# Design.net
KiCad netlist of a schematic drawn in EAGLE
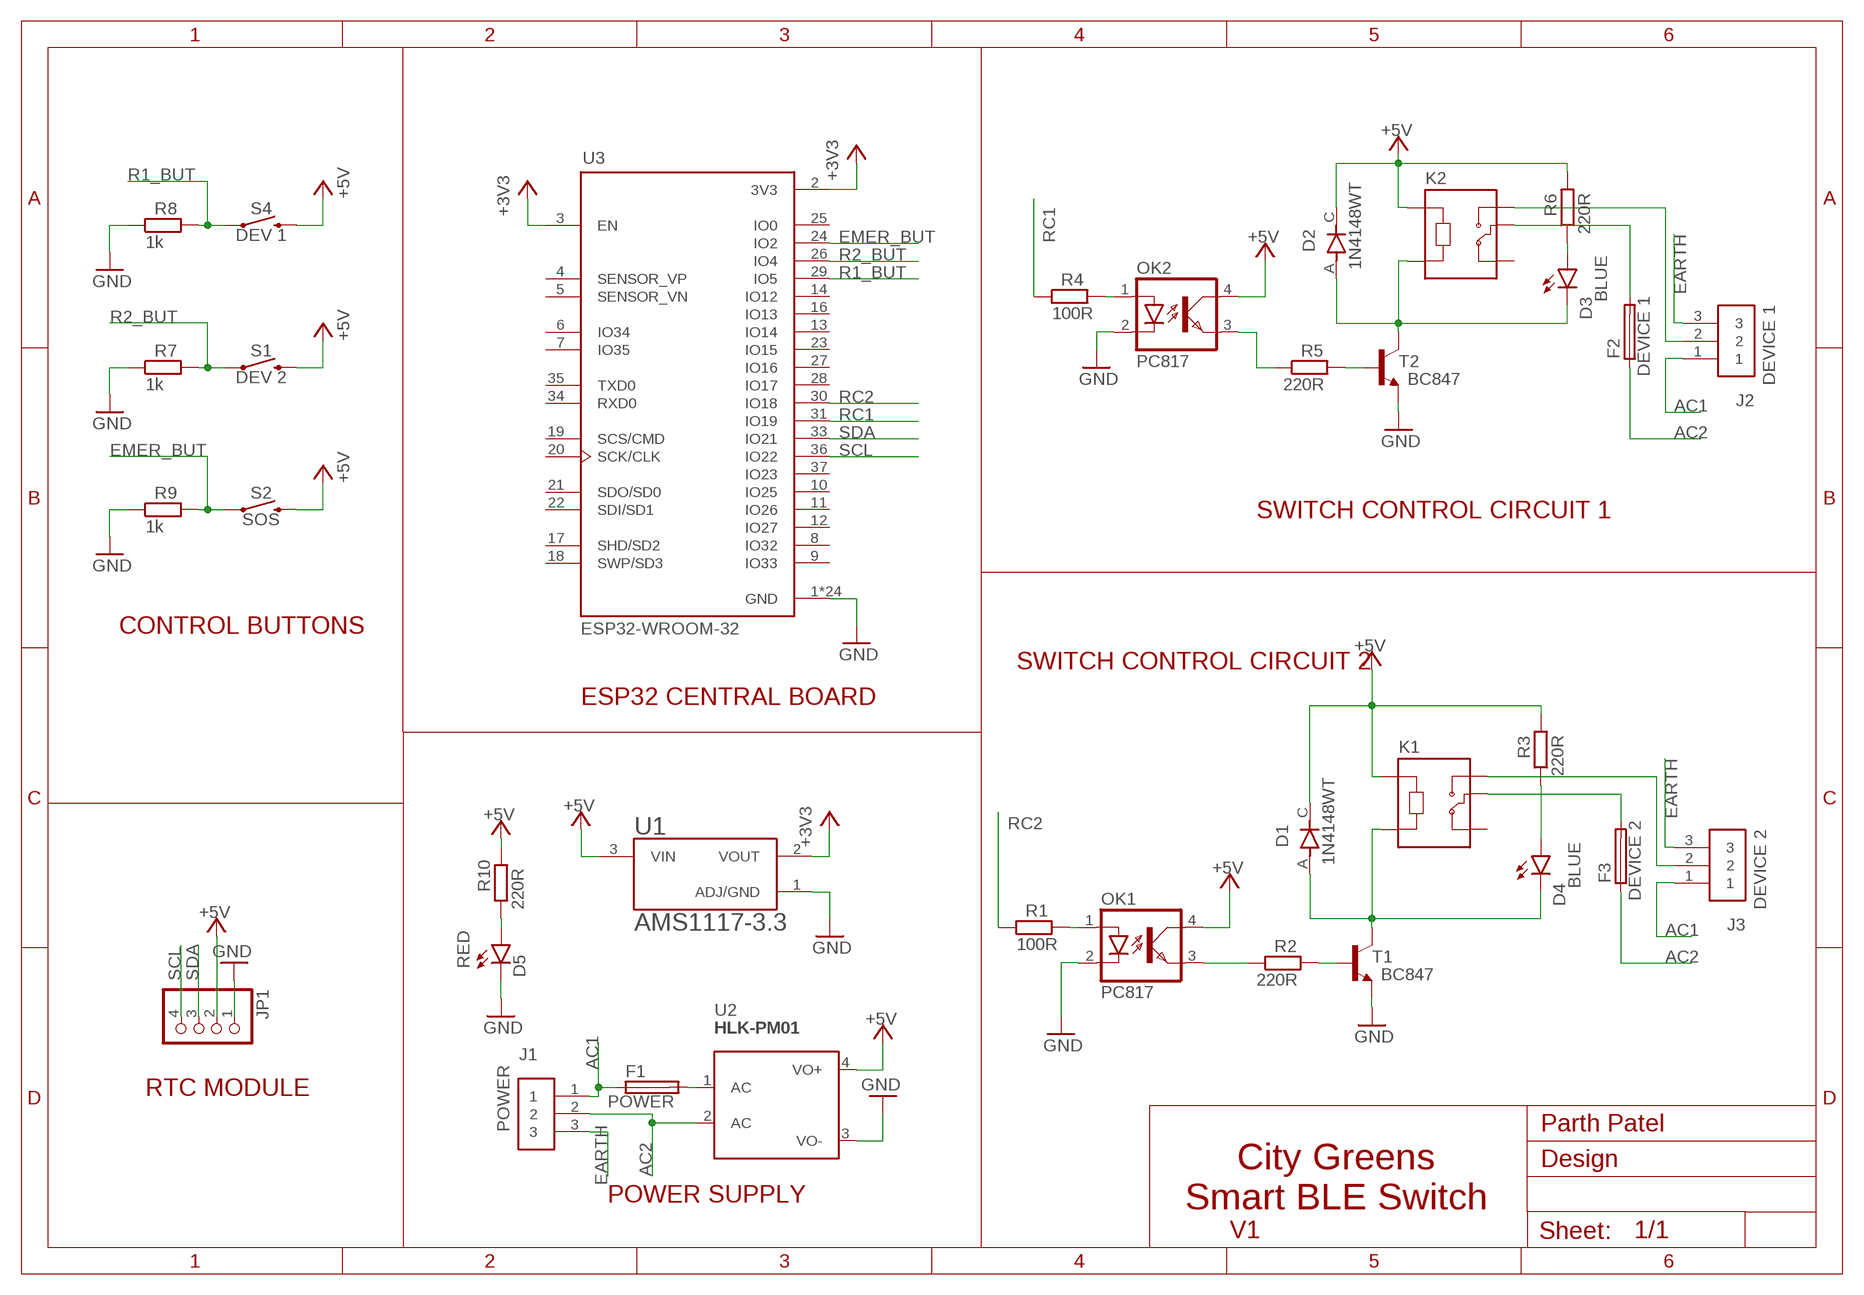
[diagram p0: schematic, sheet 1]

(export (version "E")
  (design (tool "Eeschema 10.0.6"))
  (components
    (comp (ref "D1")
      (value "1N4148WT")
      (footprint "eagle-import:SODFL1608X70N")
      (fields (field (name "MF") "ON Semiconductor"))
      (libsource (lib "eagle-import") (part "1N4148WT"))
    )
    (comp (ref "D2")
      (value "1N4148WT")
      (footprint "eagle-import:SODFL1608X70N")
      (fields (field (name "MF") "ON Semiconductor") (field (name "SPICEPREFIX") "D"))
      (libsource (lib "eagle-import") (part "1N4148WT"))
    )
    (comp (ref "D3")
      (value "BLUE")
      (footprint "eagle-import:CHIP-LED0603")
      (libsource (lib "eagle-import") (part "LEDCHIP-LED0603"))
    )
    (comp (ref "D4")
      (value "BLUE")
      (footprint "eagle-import:CHIP-LED0603")
      (libsource (lib "eagle-import") (part "LEDCHIP-LED0603"))
    )
    (comp (ref "D5")
      (value "RED")
      (footprint "eagle-import:CHIP-LED0603")
      (libsource (lib "eagle-import") (part "LEDCHIP-LED0603"))
    )
    (comp (ref "F1")
      (value "POWER")
      (footprint "eagle-import:TE5")
      (libsource (lib "eagle-import") (part "TE5"))
    )
    (comp (ref "F2")
      (value "DEVICE 1")
      (footprint "eagle-import:TE5")
      (libsource (lib "eagle-import") (part "TE5"))
    )
    (comp (ref "F3")
      (value "DEVICE 2")
      (footprint "eagle-import:TE5")
      (libsource (lib "eagle-import") (part "TE5"))
    )
    (comp (ref "J1")
      (value "POWER")
      (footprint "eagle-import:TERMINALBLOCK_PLUGGABLE-3-7.62MM")
      (fields
        (field (name "DIGIKEY_PART_NO") "732-2824-ND")
        (field (name "MANUFACTURER") "WURTH ELEKTRONIK")
        (field (name "MPN") "691311400103")
        (field (name "CREATED_BY") "PCBLayout.com")
      )
      (libsource (lib "eagle-import") (part "691311400103"))
    )
    (comp (ref "J2")
      (value "DEVICE 1")
      (footprint "eagle-import:TERMINALBLOCK_PLUGGABLE-3-7.62MM")
      (fields
        (field (name "DIGIKEY_PART_NO") "732-2824-ND")
        (field (name "MANUFACTURER") "WURTH ELEKTRONIK")
        (field (name "MPN") "691311400103")
        (field (name "CREATED_BY") "PCBLayout.com")
      )
      (libsource (lib "eagle-import") (part "691311400103"))
    )
    (comp (ref "J3")
      (value "DEVICE 2")
      (footprint "eagle-import:TERMINALBLOCK_PLUGGABLE-3-7.62MM")
      (fields
        (field (name "DIGIKEY_PART_NO") "732-2824-ND")
        (field (name "MANUFACTURER") "WURTH ELEKTRONIK")
        (field (name "MPN") "691311400103")
        (field (name "CREATED_BY") "PCBLayout.com")
      )
      (libsource (lib "eagle-import") (part "691311400103"))
    )
    (comp (ref "JP1")
      (value "PINHD-1X4")
      (footprint "eagle-import:1X04")
      (libsource (lib "eagle-import") (part "PINHD-1X4"))
    )
    (comp (ref "K1")
      (value "SRD-05VDC-SL-C")
      (footprint "eagle-import:RELAY_SRD-05VDC-SL-C")
      (fields (field (name "MF") "Songle Relay"))
      (libsource (lib "eagle-import") (part "SRD-05VDC-SL-C"))
    )
    (comp (ref "K2")
      (value "SRD-05VDC-SL-C")
      (footprint "eagle-import:RELAY_SRD-05VDC-SL-C")
      (fields (field (name "MF") "Songle Relay"))
      (libsource (lib "eagle-import") (part "SRD-05VDC-SL-C"))
    )
    (comp (ref "OK1")
      (value "PC817")
      (footprint "eagle-import:DIL04")
      (fields (field (name "MPN") "PC817X4J000F"))
      (libsource (lib "eagle-import") (part "PC817"))
    )
    (comp (ref "OK2")
      (value "PC817")
      (footprint "eagle-import:DIL04")
      (fields (field (name "MPN") "PC817X4J000F"))
      (libsource (lib "eagle-import") (part "PC817"))
    )
    (comp (ref "R1")
      (value "100R")
      (footprint "eagle-import:R0805")
      (libsource (lib "eagle-import") (part "R-EU_R0805"))
    )
    (comp (ref "R2")
      (value "220R")
      (footprint "eagle-import:R0805")
      (libsource (lib "eagle-import") (part "R-EU_R0805"))
    )
    (comp (ref "R3")
      (value "220R")
      (footprint "eagle-import:R0805")
      (libsource (lib "eagle-import") (part "R-EU_R0805"))
    )
    (comp (ref "R4")
      (value "100R")
      (footprint "eagle-import:R0805")
      (libsource (lib "eagle-import") (part "R-EU_R0805"))
    )
    (comp (ref "R5")
      (value "220R")
      (footprint "eagle-import:R0805")
      (libsource (lib "eagle-import") (part "R-EU_R0805"))
    )
    (comp (ref "R6")
      (value "220R")
      (footprint "eagle-import:R0805")
      (libsource (lib "eagle-import") (part "R-EU_R0805"))
    )
    (comp (ref "R7")
      (value "1k")
      (footprint "eagle-import:R0805")
      (libsource (lib "eagle-import") (part "R-EU_R0805"))
    )
    (comp (ref "R8")
      (value "1k")
      (footprint "eagle-import:R0805")
      (libsource (lib "eagle-import") (part "R-EU_R0805"))
    )
    (comp (ref "R9")
      (value "1k")
      (footprint "eagle-import:R0805")
      (libsource (lib "eagle-import") (part "R-EU_R0805"))
    )
    (comp (ref "R10")
      (value "220R")
      (footprint "eagle-import:R0805")
      (libsource (lib "eagle-import") (part "R-EU_R0805"))
    )
    (comp (ref "S1")
      (value "DEV 2")
      (footprint "eagle-import:TACTILE_SWITCH_SMD_4.5MM")
      (libsource (lib "eagle-import") (part "MOMENTARY-SWITCH-SPST-SMD-4.5MM"))
    )
    (comp (ref "S2")
      (value "SOS")
      (footprint "eagle-import:TACTILE_SWITCH_SMD_4.5MM")
      (libsource (lib "eagle-import") (part "MOMENTARY-SWITCH-SPST-SMD-4.5MM"))
    )
    (comp (ref "S4")
      (value "DEV 1")
      (footprint "eagle-import:TACTILE_SWITCH_SMD_4.5MM")
      (libsource (lib "eagle-import") (part "MOMENTARY-SWITCH-SPST-SMD-4.5MM"))
    )
    (comp (ref "T1")
      (value "BC847")
      (footprint "eagle-import:SOT23")
      (libsource (lib "eagle-import") (part "BC847"))
    )
    (comp (ref "T2")
      (value "BC847")
      (footprint "eagle-import:SOT23")
      (libsource (lib "eagle-import") (part "BC847"))
    )
    (comp (ref "U1")
      (value "AMS1117-3.3")
      (footprint "eagle-import:SOT229P700X180-4N")
      (fields (field (name "MF") "AMD"))
      (libsource (lib "eagle-import") (part "AMS1117-3.3"))
    )
    (comp (ref "U2")
      (value "HLK-PM01")
      (footprint "eagle-import:HLK-PM01")
      (fields (field (name "MF") "Hi-link") (field (name "MP") "hlk-pm01"))
      (libsource (lib "eagle-import") (part "HLK-PM01"))
    )
    (comp (ref "U3")
      (value "ESP32-WROOM-32")
      (footprint "eagle-import:MODULE_ESP32-WROOM-32")
      (fields (field (name "MF") "Espressif Systems"))
      (libsource (lib "eagle-import") (part "ESP32-WROOM-32"))
    )
  )
  (nets
    (net (code "1") (name "+3V3") (class "Default")
      (node (ref "U1") (pin "2") (pinfunction "VOUT_2") (pintype "output"))
      (node (ref "U3") (pin "2") (pinfunction "3V3_2") (pintype "power_in"))
      (node (ref "U3") (pin "3") (pinfunction "EN_3") (pintype "input"))
    )
    (net (code "2") (name "+5V") (class "Default")
      (node (ref "D1") (pin "C") (pinfunction "C_C") (pintype "passive"))
      (node (ref "D2") (pin "C") (pinfunction "C_C") (pintype "passive"))
      (node (ref "JP1") (pin "2") (pinfunction "2_2") (pintype "passive"))
      (node (ref "K1") (pin "A1") (pinfunction "A1_A1") (pintype "passive"))
      (node (ref "K2") (pin "A1") (pinfunction "A1_A1") (pintype "passive"))
      (node (ref "OK1") (pin "4") (pinfunction "COL_4") (pintype "passive"))
      (node (ref "OK2") (pin "4") (pinfunction "COL_4") (pintype "passive"))
      (node (ref "R10") (pin "2") (pinfunction "2_2") (pintype "passive"))
      (node (ref "R3") (pin "2") (pinfunction "2_2") (pintype "passive"))
      (node (ref "R6") (pin "2") (pinfunction "2_2") (pintype "passive"))
      (node (ref "S1") (pin "1") (pinfunction "2_1") (pintype "passive"))
      (node (ref "S1") (pin "4") (pinfunction "2_4") (pintype "passive"))
      (node (ref "S2") (pin "1") (pinfunction "2_1") (pintype "passive"))
      (node (ref "S2") (pin "4") (pinfunction "2_4") (pintype "passive"))
      (node (ref "S4") (pin "1") (pinfunction "2_1") (pintype "passive"))
      (node (ref "S4") (pin "4") (pinfunction "2_4") (pintype "passive"))
      (node (ref "U1") (pin "3") (pinfunction "VIN_3") (pintype "input"))
      (node (ref "U2") (pin "4") (pinfunction "VO+_4") (pintype "bidirectional"))
    )
    (net (code "3") (name "/AC1") (class "Default")
      (node (ref "F1") (pin "1") (pinfunction "1_1") (pintype "passive"))
      (node (ref "J1") (pin "1") (pinfunction "1_1") (pintype "passive"))
      (node (ref "J2") (pin "1") (pinfunction "1_1") (pintype "passive"))
      (node (ref "J3") (pin "1") (pinfunction "1_1") (pintype "passive"))
    )
    (net (code "4") (name "/AC2") (class "Default")
      (node (ref "F2") (pin "1") (pinfunction "1_1") (pintype "passive"))
      (node (ref "F3") (pin "1") (pinfunction "1_1") (pintype "passive"))
      (node (ref "J1") (pin "2") (pinfunction "2_2") (pintype "passive"))
      (node (ref "U2") (pin "2") (pinfunction "AC_2") (pintype "bidirectional"))
    )
    (net (code "5") (name "/EARTH") (class "Default")
      (node (ref "J1") (pin "3") (pinfunction "3_3") (pintype "passive"))
      (node (ref "J2") (pin "3") (pinfunction "3_3") (pintype "passive"))
      (node (ref "J3") (pin "3") (pinfunction "3_3") (pintype "passive"))
    )
    (net (code "6") (name "/EMER_BUT") (class "Default")
      (node (ref "R9") (pin "2") (pinfunction "2_2") (pintype "passive"))
      (node (ref "S2") (pin "2") (pinfunction "1_2") (pintype "passive"))
      (node (ref "S2") (pin "3") (pinfunction "1_3") (pintype "passive"))
      (node (ref "U3") (pin "24") (pinfunction "IO2_24") (pintype "bidirectional"))
    )
    (net (code "7") (name "/R1_BUT") (class "Default")
      (node (ref "R8") (pin "2") (pinfunction "2_2") (pintype "passive"))
      (node (ref "S4") (pin "2") (pinfunction "1_2") (pintype "passive"))
      (node (ref "S4") (pin "3") (pinfunction "1_3") (pintype "passive"))
      (node (ref "U3") (pin "29") (pinfunction "IO5_29") (pintype "bidirectional"))
    )
    (net (code "8") (name "/R2_BUT") (class "Default")
      (node (ref "R7") (pin "2") (pinfunction "2_2") (pintype "passive"))
      (node (ref "S1") (pin "2") (pinfunction "1_2") (pintype "passive"))
      (node (ref "S1") (pin "3") (pinfunction "1_3") (pintype "passive"))
      (node (ref "U3") (pin "26") (pinfunction "IO4_26") (pintype "bidirectional"))
    )
    (net (code "9") (name "/RC1") (class "Default")
      (node (ref "R4") (pin "1") (pinfunction "1_1") (pintype "passive"))
      (node (ref "U3") (pin "31") (pinfunction "IO19_31") (pintype "bidirectional"))
    )
    (net (code "10") (name "/RC2") (class "Default")
      (node (ref "R1") (pin "1") (pinfunction "1_1") (pintype "passive"))
      (node (ref "U3") (pin "30") (pinfunction "IO18_30") (pintype "bidirectional"))
    )
    (net (code "11") (name "/SCL") (class "Default")
      (node (ref "JP1") (pin "4") (pinfunction "4_4") (pintype "passive"))
      (node (ref "U3") (pin "36") (pinfunction "IO22_36") (pintype "bidirectional"))
    )
    (net (code "12") (name "/SDA") (class "Default")
      (node (ref "JP1") (pin "3") (pinfunction "3_3") (pintype "passive"))
      (node (ref "U3") (pin "33") (pinfunction "IO21_33") (pintype "bidirectional"))
    )
    (net (code "13") (name "GND") (class "Default")
      (node (ref "D5") (pin "C") (pinfunction "C_C") (pintype "passive"))
      (node (ref "JP1") (pin "1") (pinfunction "1_1") (pintype "passive"))
      (node (ref "OK1") (pin "2") (pinfunction "C_2") (pintype "passive"))
      (node (ref "OK2") (pin "2") (pinfunction "C_2") (pintype "passive"))
      (node (ref "R7") (pin "1") (pinfunction "1_1") (pintype "passive"))
      (node (ref "R8") (pin "1") (pinfunction "1_1") (pintype "passive"))
      (node (ref "R9") (pin "1") (pinfunction "1_1") (pintype "passive"))
      (node (ref "T1") (pin "2") (pinfunction "E_2") (pintype "passive"))
      (node (ref "T2") (pin "2") (pinfunction "E_2") (pintype "passive"))
      (node (ref "U1") (pin "1") (pinfunction "ADJ/GND_1") (pintype "power_in"))
      (node (ref "U2") (pin "3") (pinfunction "VO-_3") (pintype "bidirectional"))
      (node (ref "U3") (pin "1") (pinfunction "GND_1") (pintype "power_in"))
      (node (ref "U3") (pin "15") (pinfunction "GND_15") (pintype "power_in"))
      (node (ref "U3") (pin "38") (pinfunction "GND_38") (pintype "power_in"))
      (node (ref "U3") (pin "39_1") (pinfunction "GND_39_1") (pintype "power_in"))
      (node (ref "U3") (pin "39_10") (pinfunction "GND_39_10") (pintype "power_in"))
      (node (ref "U3") (pin "39_11") (pinfunction "GND_39_11") (pintype "power_in"))
      (node (ref "U3") (pin "39_12") (pinfunction "GND_39_12") (pintype "power_in"))
      (node (ref "U3") (pin "39_13") (pinfunction "GND_39_13") (pintype "power_in"))
      (node (ref "U3") (pin "39_14") (pinfunction "GND_39_14") (pintype "power_in"))
      (node (ref "U3") (pin "39_15") (pinfunction "GND_39_15") (pintype "power_in"))
      (node (ref "U3") (pin "39_16") (pinfunction "GND_39_16") (pintype "power_in"))
      (node (ref "U3") (pin "39_17") (pinfunction "GND_39_17") (pintype "power_in"))
      (node (ref "U3") (pin "39_18") (pinfunction "GND_39_18") (pintype "power_in"))
      (node (ref "U3") (pin "39_19") (pinfunction "GND_39_19") (pintype "power_in"))
      (node (ref "U3") (pin "39_2") (pinfunction "GND_39_2") (pintype "power_in"))
      (node (ref "U3") (pin "39_20") (pinfunction "GND_39_20") (pintype "power_in"))
      (node (ref "U3") (pin "39_21") (pinfunction "GND_39_21") (pintype "power_in"))
      (node (ref "U3") (pin "39_3") (pinfunction "GND_39_3") (pintype "power_in"))
      (node (ref "U3") (pin "39_4") (pinfunction "GND_39_4") (pintype "power_in"))
      (node (ref "U3") (pin "39_5") (pinfunction "GND_39_5") (pintype "power_in"))
      (node (ref "U3") (pin "39_6") (pinfunction "GND_39_6") (pintype "power_in"))
      (node (ref "U3") (pin "39_7") (pinfunction "GND_39_7") (pintype "power_in"))
      (node (ref "U3") (pin "39_8") (pinfunction "GND_39_8") (pintype "power_in"))
      (node (ref "U3") (pin "39_9") (pinfunction "GND_39_9") (pintype "power_in"))
    )
    (net (code "14") (name "Net-(D3-PadA)") (class "Default")
      (node (ref "D3") (pin "A") (pinfunction "A_A") (pintype "passive"))
      (node (ref "R6") (pin "1") (pinfunction "1_1") (pintype "passive"))
    )
    (net (code "15") (name "Net-(D4-PadA)") (class "Default")
      (node (ref "D4") (pin "A") (pinfunction "A_A") (pintype "passive"))
      (node (ref "R3") (pin "1") (pinfunction "1_1") (pintype "passive"))
    )
    (net (code "16") (name "Net-(D5-PadA)") (class "Default")
      (node (ref "D5") (pin "A") (pinfunction "A_A") (pintype "passive"))
      (node (ref "R10") (pin "1") (pinfunction "1_1") (pintype "passive"))
    )
    (net (code "17") (name "Net-(F1-Pad2)") (class "Default")
      (node (ref "F1") (pin "2") (pinfunction "2_2") (pintype "passive"))
      (node (ref "U2") (pin "1") (pinfunction "AC_1") (pintype "bidirectional"))
    )
    (net (code "18") (name "Net-(F2-Pad2)") (class "Default")
      (node (ref "F2") (pin "2") (pinfunction "2_2") (pintype "passive"))
      (node (ref "K2") (pin "COM") (pinfunction "COM_COM") (pintype "passive"))
    )
    (net (code "19") (name "Net-(F3-Pad2)") (class "Default")
      (node (ref "F3") (pin "2") (pinfunction "2_2") (pintype "passive"))
      (node (ref "K1") (pin "COM") (pinfunction "COM_COM") (pintype "passive"))
    )
    (net (code "20") (name "Net-(J2-Pad2)") (class "Default")
      (node (ref "J2") (pin "2") (pinfunction "2_2") (pintype "passive"))
      (node (ref "K2") (pin "NO") (pinfunction "NO_NO") (pintype "passive"))
    )
    (net (code "21") (name "Net-(J3-Pad2)") (class "Default")
      (node (ref "J3") (pin "2") (pinfunction "2_2") (pintype "passive"))
      (node (ref "K1") (pin "NO") (pinfunction "NO_NO") (pintype "passive"))
    )
    (net (code "22") (name "Net-(OK1-A)") (class "Default")
      (node (ref "OK1") (pin "1") (pinfunction "A_1") (pintype "passive"))
      (node (ref "R1") (pin "2") (pinfunction "2_2") (pintype "passive"))
    )
    (net (code "23") (name "Net-(OK1-EMIT)") (class "Default")
      (node (ref "OK1") (pin "3") (pinfunction "EMIT_3") (pintype "passive"))
      (node (ref "R2") (pin "1") (pinfunction "1_1") (pintype "passive"))
    )
    (net (code "24") (name "Net-(OK2-A)") (class "Default")
      (node (ref "OK2") (pin "1") (pinfunction "A_1") (pintype "passive"))
      (node (ref "R4") (pin "2") (pinfunction "2_2") (pintype "passive"))
    )
    (net (code "25") (name "Net-(OK2-EMIT)") (class "Default")
      (node (ref "OK2") (pin "3") (pinfunction "EMIT_3") (pintype "passive"))
      (node (ref "R5") (pin "1") (pinfunction "1_1") (pintype "passive"))
    )
    (net (code "26") (name "Net-(T1-B)") (class "Default")
      (node (ref "R2") (pin "2") (pinfunction "2_2") (pintype "passive"))
      (node (ref "T1") (pin "1") (pinfunction "B_1") (pintype "passive"))
    )
    (net (code "27") (name "Net-(T1-C)") (class "Default")
      (node (ref "D1") (pin "A") (pinfunction "A_A") (pintype "passive"))
      (node (ref "D4") (pin "C") (pinfunction "C_C") (pintype "passive"))
      (node (ref "K1") (pin "A2") (pinfunction "A2_A2") (pintype "passive"))
      (node (ref "T1") (pin "3") (pinfunction "C_3") (pintype "passive"))
    )
    (net (code "28") (name "Net-(T2-B)") (class "Default")
      (node (ref "R5") (pin "2") (pinfunction "2_2") (pintype "passive"))
      (node (ref "T2") (pin "1") (pinfunction "B_1") (pintype "passive"))
    )
    (net (code "29") (name "Net-(T2-C)") (class "Default")
      (node (ref "D2") (pin "A") (pinfunction "A_A") (pintype "passive"))
      (node (ref "D3") (pin "C") (pinfunction "C_C") (pintype "passive"))
      (node (ref "K2") (pin "A2") (pinfunction "A2_A2") (pintype "passive"))
      (node (ref "T2") (pin "3") (pinfunction "C_3") (pintype "passive"))
    )
    (net (code "30") (name "unconnected-(K1-PadNC)") (class "Default")
      (node (ref "K1") (pin "NC") (pinfunction "NC_NC") (pintype "passive"))
    )
    (net (code "31") (name "unconnected-(K2-PadNC)") (class "Default")
      (node (ref "K2") (pin "NC") (pinfunction "NC_NC") (pintype "passive"))
    )
    (net (code "32") (name "unconnected-(U3-IO0-Pad25)") (class "Default")
      (node (ref "U3") (pin "25") (pinfunction "IO0_25") (pintype "bidirectional"))
    )
    (net (code "33") (name "unconnected-(U3-IO12-Pad14)") (class "Default")
      (node (ref "U3") (pin "14") (pinfunction "IO12_14") (pintype "bidirectional"))
    )
    (net (code "34") (name "unconnected-(U3-IO13-Pad16)") (class "Default")
      (node (ref "U3") (pin "16") (pinfunction "IO13_16") (pintype "bidirectional"))
    )
    (net (code "35") (name "unconnected-(U3-IO14-Pad13)") (class "Default")
      (node (ref "U3") (pin "13") (pinfunction "IO14_13") (pintype "bidirectional"))
    )
    (net (code "36") (name "unconnected-(U3-IO15-Pad23)") (class "Default")
      (node (ref "U3") (pin "23") (pinfunction "IO15_23") (pintype "bidirectional"))
    )
    (net (code "37") (name "unconnected-(U3-IO16-Pad27)") (class "Default")
      (node (ref "U3") (pin "27") (pinfunction "IO16_27") (pintype "bidirectional"))
    )
    (net (code "38") (name "unconnected-(U3-IO17-Pad28)") (class "Default")
      (node (ref "U3") (pin "28") (pinfunction "IO17_28") (pintype "bidirectional"))
    )
    (net (code "39") (name "unconnected-(U3-IO23-Pad37)") (class "Default")
      (node (ref "U3") (pin "37") (pinfunction "IO23_37") (pintype "bidirectional"))
    )
    (net (code "40") (name "unconnected-(U3-IO25-Pad10)") (class "Default")
      (node (ref "U3") (pin "10") (pinfunction "IO25_10") (pintype "bidirectional"))
    )
    (net (code "41") (name "unconnected-(U3-IO26-Pad11)") (class "Default")
      (node (ref "U3") (pin "11") (pinfunction "IO26_11") (pintype "bidirectional"))
    )
    (net (code "42") (name "unconnected-(U3-IO27-Pad12)") (class "Default")
      (node (ref "U3") (pin "12") (pinfunction "IO27_12") (pintype "bidirectional"))
    )
    (net (code "43") (name "unconnected-(U3-IO32-Pad8)") (class "Default")
      (node (ref "U3") (pin "8") (pinfunction "IO32_8") (pintype "bidirectional"))
    )
    (net (code "44") (name "unconnected-(U3-IO33-Pad9)") (class "Default")
      (node (ref "U3") (pin "9") (pinfunction "IO33_9") (pintype "bidirectional"))
    )
    (net (code "45") (name "unconnected-(U3-IO34-Pad6)") (class "Default")
      (node (ref "U3") (pin "6") (pinfunction "IO34_6") (pintype "input"))
    )
    (net (code "46") (name "unconnected-(U3-IO35-Pad7)") (class "Default")
      (node (ref "U3") (pin "7") (pinfunction "IO35_7") (pintype "input"))
    )
    (net (code "47") (name "unconnected-(U3-RXD0-Pad34)") (class "Default")
      (node (ref "U3") (pin "34") (pinfunction "RXD0_34") (pintype "bidirectional"))
    )
    (net (code "48") (name "unconnected-(U3-SCK{slash}CLK-Pad20)") (class "Default")
      (node (ref "U3") (pin "20") (pinfunction "SCK/CLK_20") (pintype "bidirectional"))
    )
    (net (code "49") (name "unconnected-(U3-SCS{slash}CMD-Pad19)") (class "Default")
      (node (ref "U3") (pin "19") (pinfunction "SCS/CMD_19") (pintype "bidirectional"))
    )
    (net (code "50") (name "unconnected-(U3-SDI{slash}SD1-Pad22)") (class "Default")
      (node (ref "U3") (pin "22") (pinfunction "SDI/SD1_22") (pintype "bidirectional"))
    )
    (net (code "51") (name "unconnected-(U3-SDO{slash}SD0-Pad21)") (class "Default")
      (node (ref "U3") (pin "21") (pinfunction "SDO/SD0_21") (pintype "bidirectional"))
    )
    (net (code "52") (name "unconnected-(U3-SENSOR_VN-Pad5)") (class "Default")
      (node (ref "U3") (pin "5") (pinfunction "SENSOR_VN_5") (pintype "input"))
    )
    (net (code "53") (name "unconnected-(U3-SENSOR_VP-Pad4)") (class "Default")
      (node (ref "U3") (pin "4") (pinfunction "SENSOR_VP_4") (pintype "input"))
    )
    (net (code "54") (name "unconnected-(U3-SHD{slash}SD2-Pad17)") (class "Default")
      (node (ref "U3") (pin "17") (pinfunction "SHD/SD2_17") (pintype "bidirectional"))
    )
    (net (code "55") (name "unconnected-(U3-SWP{slash}SD3-Pad18)") (class "Default")
      (node (ref "U3") (pin "18") (pinfunction "SWP/SD3_18") (pintype "bidirectional"))
    )
    (net (code "56") (name "unconnected-(U3-TXD0-Pad35)") (class "Default")
      (node (ref "U3") (pin "35") (pinfunction "TXD0_35") (pintype "bidirectional"))
    )
  )
)
